# SCH_B_Register_2021-10-06.net
KiCad netlist of a schematic drawn in EasyEDA
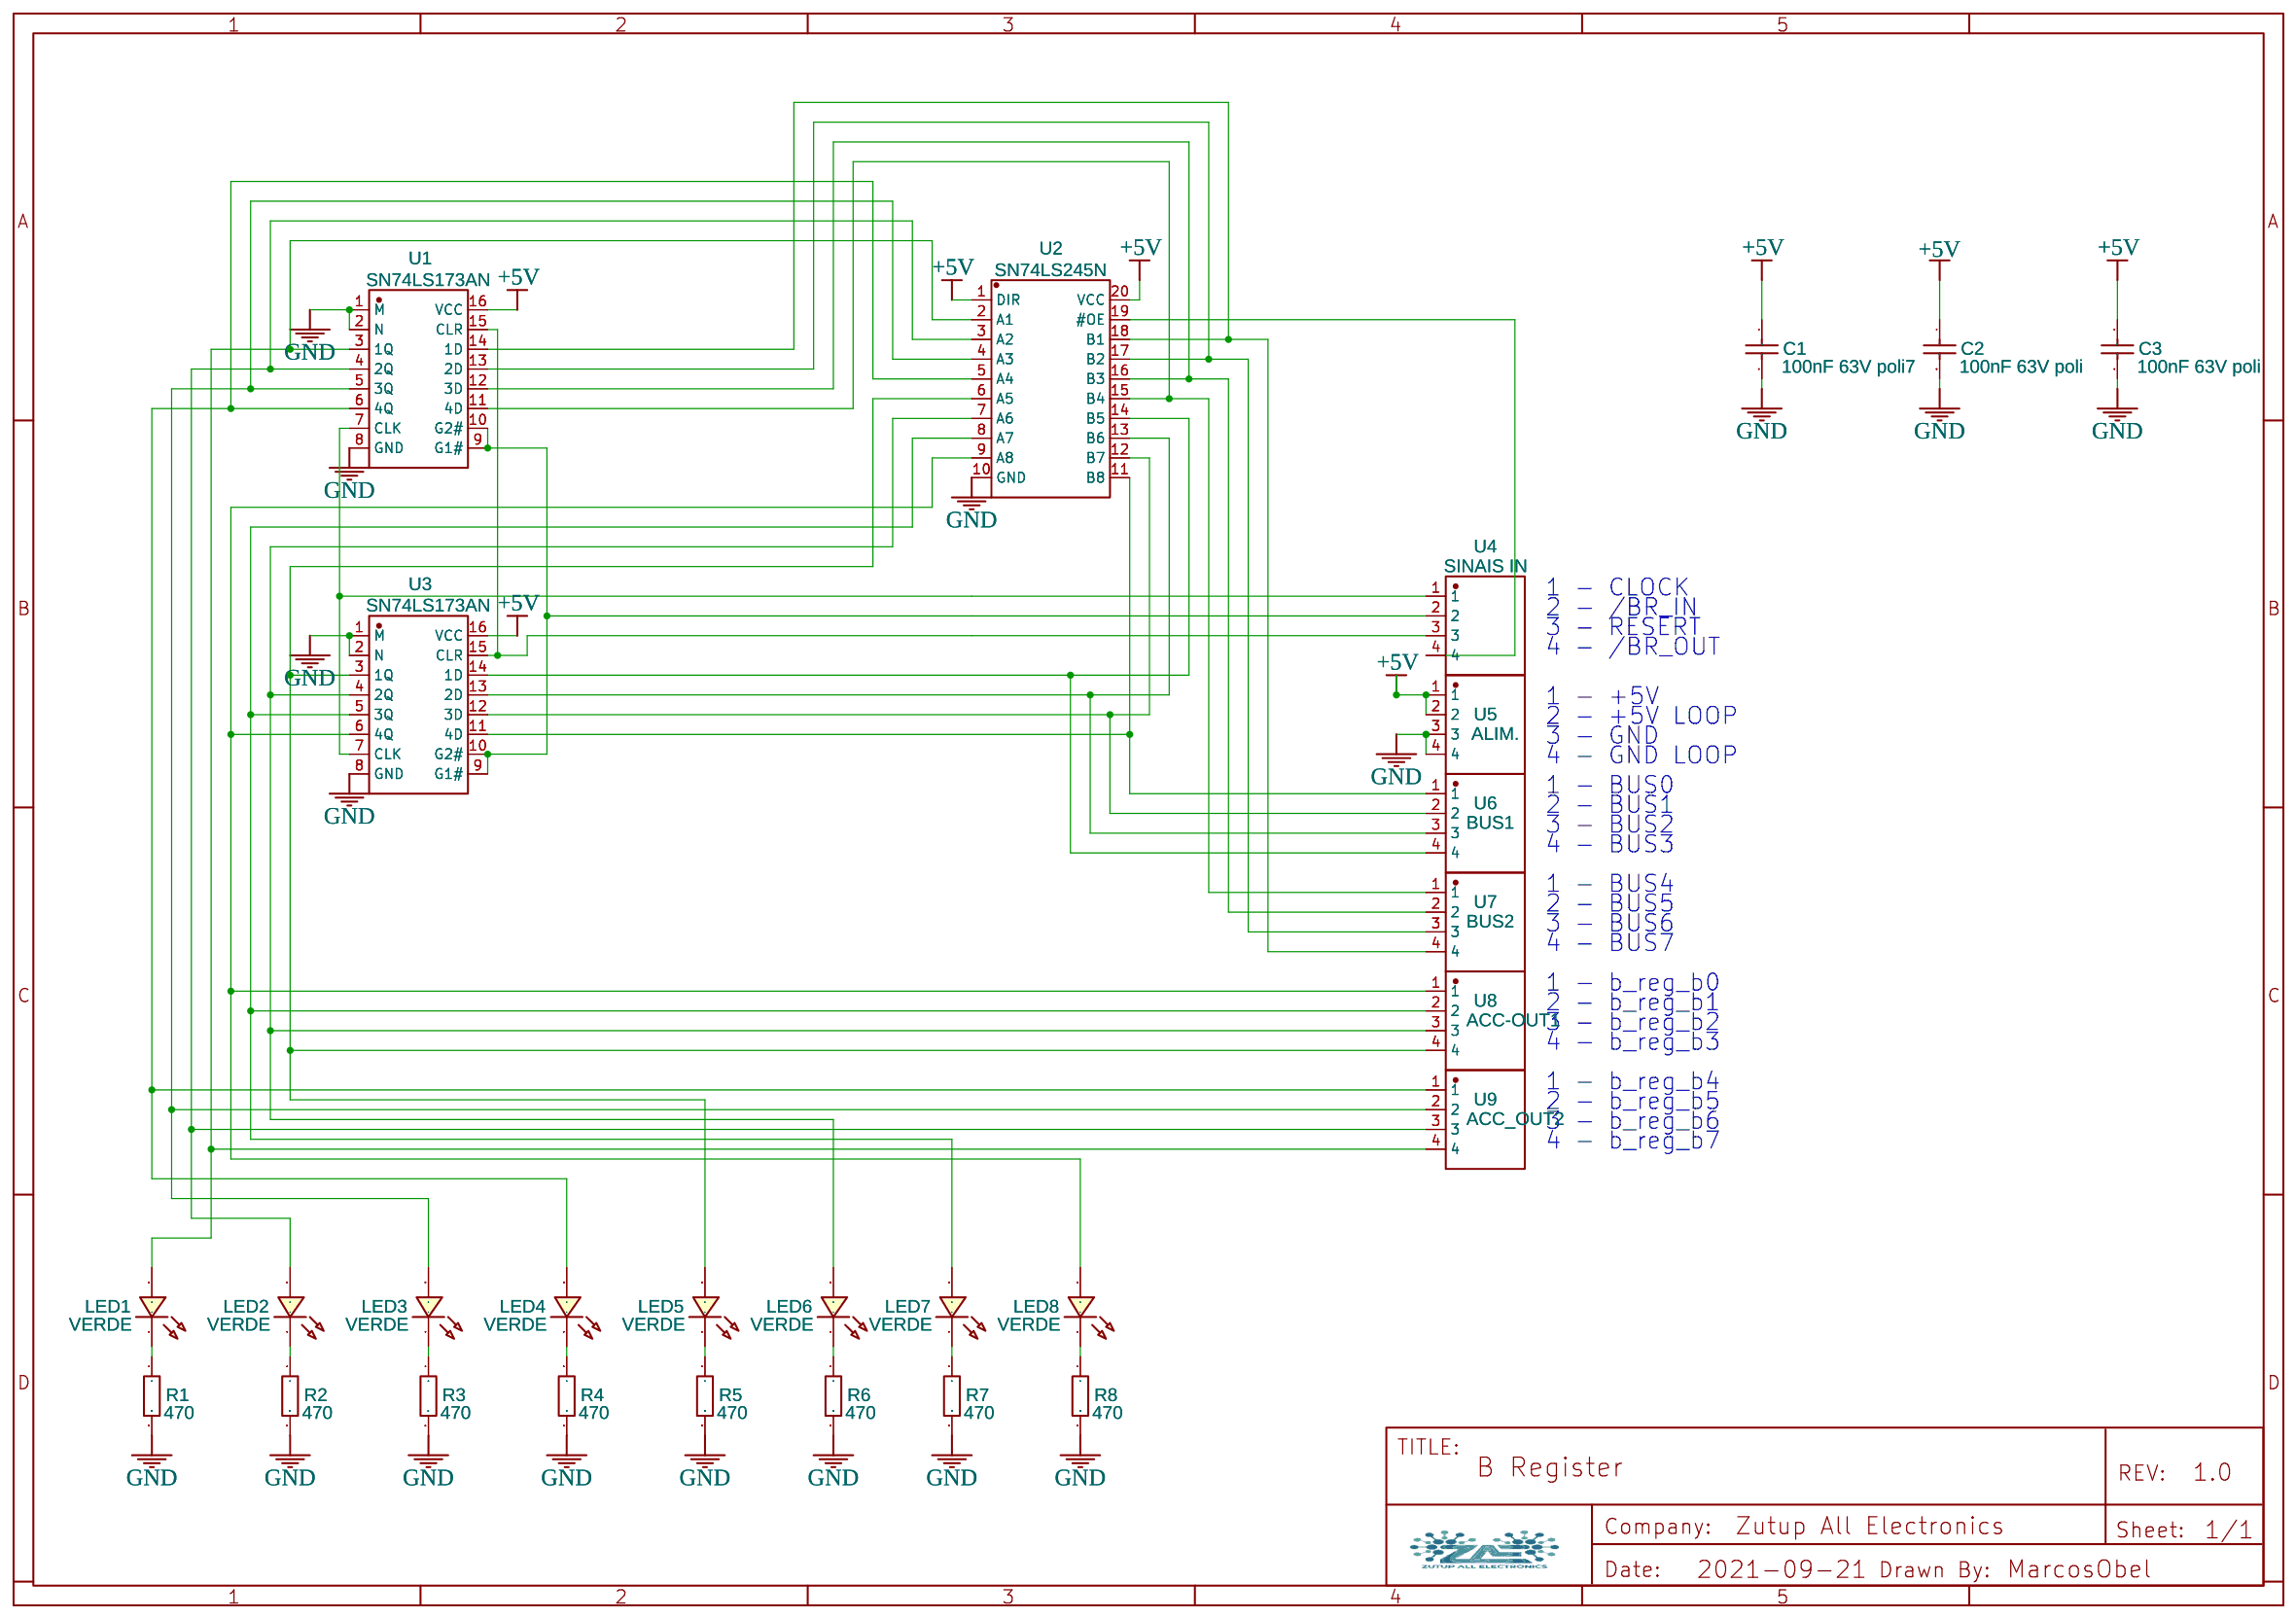
[diagram p0: schematic sheet]

(export (version "E")
  (design (tool "Eeschema 10.0.6"))
  (components
    (comp (ref "C1")
      (value "100nF 63V poli7")
      (fields
        (field (name "BOM_Manufacturer Part") "SR305C105KAR")
        (field (name "BOM_Supplier Part") "C444741")
      )
      (libsource (lib "") (part "SR305C105KAR"))
    )
    (comp (ref "C2")
      (value "100nF 63V poli")
      (fields
        (field (name "BOM_Manufacturer Part") "SR305C105KAR")
        (field (name "BOM_Supplier Part") "C444741")
      )
      (libsource (lib "") (part "SR305C105KAR"))
    )
    (comp (ref "C3")
      (value "100nF 63V poli")
      (fields
        (field (name "BOM_Manufacturer Part") "SR305C105KAR")
        (field (name "BOM_Supplier Part") "C444741")
      )
      (libsource (lib "") (part "SR305C105KAR"))
    )
    (comp (ref "LED1")
      (value "VERDE")
      (fields (field (name "BOM_Manufacturer Part") "264-7GD") (field (name "BOM_Supplier Part") "C605465"))
      (libsource (lib "") (part "264-7GD"))
    )
    (comp (ref "LED2")
      (value "VERDE")
      (fields (field (name "BOM_Manufacturer Part") "264-7GD") (field (name "BOM_Supplier Part") "C605465"))
      (libsource (lib "") (part "264-7GD"))
    )
    (comp (ref "LED3")
      (value "VERDE")
      (fields (field (name "BOM_Manufacturer Part") "264-7GD") (field (name "BOM_Supplier Part") "C605465"))
      (libsource (lib "") (part "264-7GD"))
    )
    (comp (ref "LED4")
      (value "VERDE")
      (fields (field (name "BOM_Manufacturer Part") "264-7GD") (field (name "BOM_Supplier Part") "C605465"))
      (libsource (lib "") (part "264-7GD"))
    )
    (comp (ref "LED5")
      (value "VERDE")
      (fields (field (name "BOM_Manufacturer Part") "264-7GD") (field (name "BOM_Supplier Part") "C605465"))
      (libsource (lib "") (part "264-7GD"))
    )
    (comp (ref "LED6")
      (value "VERDE")
      (fields (field (name "BOM_Manufacturer Part") "264-7GD") (field (name "BOM_Supplier Part") "C605465"))
      (libsource (lib "") (part "264-7GD"))
    )
    (comp (ref "LED7")
      (value "VERDE")
      (fields (field (name "BOM_Manufacturer Part") "264-7GD") (field (name "BOM_Supplier Part") "C605465"))
      (libsource (lib "") (part "264-7GD"))
    )
    (comp (ref "LED8")
      (value "VERDE")
      (fields (field (name "BOM_Manufacturer Part") "264-7GD") (field (name "BOM_Supplier Part") "C605465"))
      (libsource (lib "") (part "264-7GD"))
    )
    (comp (ref "R1")
      (value "470")
      (fields
        (field (name "BOM_Manufacturer Part") "CFR02SJ0823A10")
        (field (name "BOM_Supplier Part") "C69876")
      )
      (libsource (lib "") (part "CFR02SJ0823A10"))
    )
    (comp (ref "R2")
      (value "470")
      (fields
        (field (name "BOM_Manufacturer Part") "CFR02SJ0823A10")
        (field (name "BOM_Supplier Part") "C69876")
      )
      (libsource (lib "") (part "CFR02SJ0823A10"))
    )
    (comp (ref "R3")
      (value "470")
      (fields
        (field (name "BOM_Manufacturer Part") "CFR02SJ0823A10")
        (field (name "BOM_Supplier Part") "C69876")
      )
      (libsource (lib "") (part "CFR02SJ0823A10"))
    )
    (comp (ref "R4")
      (value "470")
      (fields
        (field (name "BOM_Manufacturer Part") "CFR02SJ0823A10")
        (field (name "BOM_Supplier Part") "C69876")
      )
      (libsource (lib "") (part "CFR02SJ0823A10"))
    )
    (comp (ref "R5")
      (value "470")
      (fields
        (field (name "BOM_Manufacturer Part") "CFR02SJ0823A10")
        (field (name "BOM_Supplier Part") "C69876")
      )
      (libsource (lib "") (part "CFR02SJ0823A10"))
    )
    (comp (ref "R6")
      (value "470")
      (fields
        (field (name "BOM_Manufacturer Part") "CFR02SJ0823A10")
        (field (name "BOM_Supplier Part") "C69876")
      )
      (libsource (lib "") (part "CFR02SJ0823A10"))
    )
    (comp (ref "R7")
      (value "470")
      (fields
        (field (name "BOM_Manufacturer Part") "CFR02SJ0823A10")
        (field (name "BOM_Supplier Part") "C69876")
      )
      (libsource (lib "") (part "CFR02SJ0823A10"))
    )
    (comp (ref "R8")
      (value "470")
      (fields
        (field (name "BOM_Manufacturer Part") "CFR02SJ0823A10")
        (field (name "BOM_Supplier Part") "C69876")
      )
      (libsource (lib "") (part "CFR02SJ0823A10"))
    )
    (comp (ref "U1")
      (value "SN74LS173AN")
      (fields (field (name "BOM_Supplier Part") "C1550125"))
      (libsource (lib "") (part "SN74LS173AN"))
    )
    (comp (ref "U2")
      (value "SN74LS245N")
      (fields (field (name "BOM_Supplier Part") "C352966"))
      (libsource (lib "") (part "SN74LS245N"))
    )
    (comp (ref "U3")
      (value "SN74LS173AN")
      (fields (field (name "BOM_Supplier Part") "C1550125"))
      (libsource (lib "") (part "SN74LS173AN"))
    )
    (comp (ref "U4")
      (value "SINAIS IN")
      (fields (field (name "BOM_Manufacturer Part") "171825-4") (field (name "BOM_Supplier Part") "C210162"))
      (libsource (lib "") (part "171825-4"))
    )
    (comp (ref "U5")
      (value "ALIM.")
      (fields (field (name "BOM_Manufacturer Part") "171825-4") (field (name "BOM_Supplier Part") "C210162"))
      (libsource (lib "") (part "171825-4"))
    )
    (comp (ref "U6")
      (value "BUS1")
      (fields (field (name "BOM_Manufacturer Part") "171825-4") (field (name "BOM_Supplier Part") "C210162"))
      (libsource (lib "") (part "171825-4"))
    )
    (comp (ref "U7")
      (value "BUS2")
      (fields (field (name "BOM_Manufacturer Part") "171825-4") (field (name "BOM_Supplier Part") "C210162"))
      (libsource (lib "") (part "171825-4"))
    )
    (comp (ref "U8")
      (value "ACC-OUT1")
      (fields (field (name "BOM_Manufacturer Part") "171825-4") (field (name "BOM_Supplier Part") "C210162"))
      (libsource (lib "") (part "171825-4"))
    )
    (comp (ref "U9")
      (value "ACC_OUT2")
      (fields (field (name "BOM_Manufacturer Part") "171825-4") (field (name "BOM_Supplier Part") "C210162"))
      (libsource (lib "") (part "171825-4"))
    )
  )
  (nets
    (net (code "1") (name "+5V") (class "Default")
      (node (ref "C1") (pin "1") (pinfunction "1_1") (pintype "input"))
      (node (ref "C2") (pin "1") (pinfunction "1_1") (pintype "input"))
      (node (ref "C3") (pin "1") (pinfunction "1_1") (pintype "input"))
      (node (ref "U1") (pin "16") (pinfunction "VCC_16") (pintype "unspecified"))
      (node (ref "U2") (pin "1") (pinfunction "DIR_1") (pintype "unspecified"))
      (node (ref "U2") (pin "20") (pinfunction "VCC_20") (pintype "unspecified"))
      (node (ref "U3") (pin "16") (pinfunction "VCC_16") (pintype "unspecified"))
      (node (ref "U5") (pin "1") (pinfunction "1_1") (pintype "unspecified"))
      (node (ref "U5") (pin "2") (pinfunction "2_2") (pintype "unspecified"))
    )
    (net (code "2") (name "GND") (class "Default")
      (node (ref "C1") (pin "2") (pinfunction "2_2") (pintype "input"))
      (node (ref "C2") (pin "2") (pinfunction "2_2") (pintype "input"))
      (node (ref "C3") (pin "2") (pinfunction "2_2") (pintype "input"))
      (node (ref "R1") (pin "2") (pinfunction "2_2") (pintype "input"))
      (node (ref "R2") (pin "2") (pinfunction "2_2") (pintype "input"))
      (node (ref "R3") (pin "2") (pinfunction "2_2") (pintype "input"))
      (node (ref "R4") (pin "2") (pinfunction "2_2") (pintype "input"))
      (node (ref "R5") (pin "2") (pinfunction "2_2") (pintype "input"))
      (node (ref "R6") (pin "2") (pinfunction "2_2") (pintype "input"))
      (node (ref "R7") (pin "2") (pinfunction "2_2") (pintype "input"))
      (node (ref "R8") (pin "2") (pinfunction "2_2") (pintype "input"))
      (node (ref "U1") (pin "1") (pinfunction "M_1") (pintype "unspecified"))
      (node (ref "U1") (pin "2") (pinfunction "N_2") (pintype "unspecified"))
      (node (ref "U1") (pin "8") (pinfunction "GND_8") (pintype "unspecified"))
      (node (ref "U2") (pin "10") (pinfunction "GND_10") (pintype "unspecified"))
      (node (ref "U3") (pin "1") (pinfunction "M_1") (pintype "unspecified"))
      (node (ref "U3") (pin "2") (pinfunction "N_2") (pintype "unspecified"))
      (node (ref "U3") (pin "8") (pinfunction "GND_8") (pintype "unspecified"))
      (node (ref "U5") (pin "3") (pinfunction "3_3") (pintype "unspecified"))
      (node (ref "U5") (pin "4") (pinfunction "4_4") (pintype "unspecified"))
    )
    (net (code "3") (name "Net-(LED1-+)") (class "Default")
      (node (ref "LED1") (pin "2") (pinfunction "+_2") (pintype "unspecified"))
      (node (ref "U1") (pin "3") (pinfunction "1Q_3") (pintype "unspecified"))
      (node (ref "U2") (pin "2") (pinfunction "A1_2") (pintype "unspecified"))
      (node (ref "U9") (pin "4") (pinfunction "4_4") (pintype "unspecified"))
    )
    (net (code "4") (name "Net-(LED1--)") (class "Default")
      (node (ref "LED1") (pin "1") (pinfunction "-_1") (pintype "unspecified"))
      (node (ref "R1") (pin "1") (pinfunction "1_1") (pintype "input"))
    )
    (net (code "5") (name "Net-(LED2-+)") (class "Default")
      (node (ref "LED2") (pin "2") (pinfunction "+_2") (pintype "unspecified"))
      (node (ref "U1") (pin "4") (pinfunction "2Q_4") (pintype "unspecified"))
      (node (ref "U2") (pin "3") (pinfunction "A2_3") (pintype "unspecified"))
      (node (ref "U9") (pin "3") (pinfunction "3_3") (pintype "unspecified"))
    )
    (net (code "6") (name "Net-(LED2--)") (class "Default")
      (node (ref "LED2") (pin "1") (pinfunction "-_1") (pintype "unspecified"))
      (node (ref "R2") (pin "1") (pinfunction "1_1") (pintype "input"))
    )
    (net (code "7") (name "Net-(LED3-+)") (class "Default")
      (node (ref "LED3") (pin "2") (pinfunction "+_2") (pintype "unspecified"))
      (node (ref "U1") (pin "5") (pinfunction "3Q_5") (pintype "unspecified"))
      (node (ref "U2") (pin "4") (pinfunction "A3_4") (pintype "unspecified"))
      (node (ref "U9") (pin "2") (pinfunction "2_2") (pintype "unspecified"))
    )
    (net (code "8") (name "Net-(LED3--)") (class "Default")
      (node (ref "LED3") (pin "1") (pinfunction "-_1") (pintype "unspecified"))
      (node (ref "R3") (pin "1") (pinfunction "1_1") (pintype "input"))
    )
    (net (code "9") (name "Net-(LED4-+)") (class "Default")
      (node (ref "LED4") (pin "2") (pinfunction "+_2") (pintype "unspecified"))
      (node (ref "U1") (pin "6") (pinfunction "4Q_6") (pintype "unspecified"))
      (node (ref "U2") (pin "5") (pinfunction "A4_5") (pintype "unspecified"))
      (node (ref "U9") (pin "1") (pinfunction "1_1") (pintype "unspecified"))
    )
    (net (code "10") (name "Net-(LED4--)") (class "Default")
      (node (ref "LED4") (pin "1") (pinfunction "-_1") (pintype "unspecified"))
      (node (ref "R4") (pin "1") (pinfunction "1_1") (pintype "input"))
    )
    (net (code "11") (name "Net-(LED5-+)") (class "Default")
      (node (ref "LED5") (pin "2") (pinfunction "+_2") (pintype "unspecified"))
      (node (ref "U2") (pin "6") (pinfunction "A5_6") (pintype "unspecified"))
      (node (ref "U3") (pin "3") (pinfunction "1Q_3") (pintype "unspecified"))
      (node (ref "U8") (pin "4") (pinfunction "4_4") (pintype "unspecified"))
    )
    (net (code "12") (name "Net-(LED5--)") (class "Default")
      (node (ref "LED5") (pin "1") (pinfunction "-_1") (pintype "unspecified"))
      (node (ref "R5") (pin "1") (pinfunction "1_1") (pintype "input"))
    )
    (net (code "13") (name "Net-(LED6-+)") (class "Default")
      (node (ref "LED6") (pin "2") (pinfunction "+_2") (pintype "unspecified"))
      (node (ref "U2") (pin "7") (pinfunction "A6_7") (pintype "unspecified"))
      (node (ref "U3") (pin "4") (pinfunction "2Q_4") (pintype "unspecified"))
      (node (ref "U8") (pin "3") (pinfunction "3_3") (pintype "unspecified"))
    )
    (net (code "14") (name "Net-(LED6--)") (class "Default")
      (node (ref "LED6") (pin "1") (pinfunction "-_1") (pintype "unspecified"))
      (node (ref "R6") (pin "1") (pinfunction "1_1") (pintype "input"))
    )
    (net (code "15") (name "Net-(LED7-+)") (class "Default")
      (node (ref "LED7") (pin "2") (pinfunction "+_2") (pintype "unspecified"))
      (node (ref "U2") (pin "8") (pinfunction "A7_8") (pintype "unspecified"))
      (node (ref "U3") (pin "5") (pinfunction "3Q_5") (pintype "unspecified"))
      (node (ref "U8") (pin "2") (pinfunction "2_2") (pintype "unspecified"))
    )
    (net (code "16") (name "Net-(LED7--)") (class "Default")
      (node (ref "LED7") (pin "1") (pinfunction "-_1") (pintype "unspecified"))
      (node (ref "R7") (pin "1") (pinfunction "1_1") (pintype "input"))
    )
    (net (code "17") (name "Net-(LED8-+)") (class "Default")
      (node (ref "LED8") (pin "2") (pinfunction "+_2") (pintype "unspecified"))
      (node (ref "U2") (pin "9") (pinfunction "A8_9") (pintype "unspecified"))
      (node (ref "U3") (pin "6") (pinfunction "4Q_6") (pintype "unspecified"))
      (node (ref "U8") (pin "1") (pinfunction "1_1") (pintype "unspecified"))
    )
    (net (code "18") (name "Net-(LED8--)") (class "Default")
      (node (ref "LED8") (pin "1") (pinfunction "-_1") (pintype "unspecified"))
      (node (ref "R8") (pin "1") (pinfunction "1_1") (pintype "input"))
    )
    (net (code "19") (name "Net-(U1-1D)") (class "Default")
      (node (ref "U1") (pin "14") (pinfunction "1D_14") (pintype "unspecified"))
      (node (ref "U2") (pin "18") (pinfunction "B1_18") (pintype "unspecified"))
      (node (ref "U7") (pin "4") (pinfunction "4_4") (pintype "unspecified"))
    )
    (net (code "20") (name "Net-(U1-2D)") (class "Default")
      (node (ref "U1") (pin "13") (pinfunction "2D_13") (pintype "unspecified"))
      (node (ref "U2") (pin "17") (pinfunction "B2_17") (pintype "unspecified"))
      (node (ref "U7") (pin "3") (pinfunction "3_3") (pintype "unspecified"))
    )
    (net (code "21") (name "Net-(U1-3D)") (class "Default")
      (node (ref "U1") (pin "12") (pinfunction "3D_12") (pintype "unspecified"))
      (node (ref "U2") (pin "16") (pinfunction "B3_16") (pintype "unspecified"))
      (node (ref "U7") (pin "2") (pinfunction "2_2") (pintype "unspecified"))
    )
    (net (code "22") (name "Net-(U1-4D)") (class "Default")
      (node (ref "U1") (pin "11") (pinfunction "4D_11") (pintype "unspecified"))
      (node (ref "U2") (pin "15") (pinfunction "B4_15") (pintype "unspecified"))
      (node (ref "U7") (pin "1") (pinfunction "1_1") (pintype "unspecified"))
    )
    (net (code "23") (name "Net-(U1-CLK)") (class "Default")
      (node (ref "U1") (pin "7") (pinfunction "CLK_7") (pintype "unspecified"))
      (node (ref "U3") (pin "7") (pinfunction "CLK_7") (pintype "unspecified"))
      (node (ref "U4") (pin "1") (pinfunction "1_1") (pintype "unspecified"))
    )
    (net (code "24") (name "Net-(U1-CLR)") (class "Default")
      (node (ref "U1") (pin "15") (pinfunction "CLR_15") (pintype "unspecified"))
      (node (ref "U3") (pin "15") (pinfunction "CLR_15") (pintype "unspecified"))
      (node (ref "U4") (pin "3") (pinfunction "3_3") (pintype "unspecified"))
    )
    (net (code "25") (name "Net-(U1-G1#)") (class "Default")
      (node (ref "U1") (pin "10") (pinfunction "G2#_10") (pintype "unspecified"))
      (node (ref "U1") (pin "9") (pinfunction "G1#_9") (pintype "unspecified"))
      (node (ref "U3") (pin "10") (pinfunction "G2#_10") (pintype "unspecified"))
      (node (ref "U3") (pin "9") (pinfunction "G1#_9") (pintype "unspecified"))
      (node (ref "U4") (pin "2") (pinfunction "2_2") (pintype "unspecified"))
    )
    (net (code "26") (name "Net-(U2-#OE)") (class "Default")
      (node (ref "U2") (pin "19") (pinfunction "#OE_19") (pintype "unspecified"))
      (node (ref "U4") (pin "4") (pinfunction "4_4") (pintype "unspecified"))
    )
    (net (code "27") (name "Net-(U2-B5)") (class "Default")
      (node (ref "U2") (pin "14") (pinfunction "B5_14") (pintype "unspecified"))
      (node (ref "U3") (pin "14") (pinfunction "1D_14") (pintype "unspecified"))
      (node (ref "U6") (pin "4") (pinfunction "4_4") (pintype "unspecified"))
    )
    (net (code "28") (name "Net-(U2-B6)") (class "Default")
      (node (ref "U2") (pin "13") (pinfunction "B6_13") (pintype "unspecified"))
      (node (ref "U3") (pin "13") (pinfunction "2D_13") (pintype "unspecified"))
      (node (ref "U6") (pin "3") (pinfunction "3_3") (pintype "unspecified"))
    )
    (net (code "29") (name "Net-(U2-B7)") (class "Default")
      (node (ref "U2") (pin "12") (pinfunction "B7_12") (pintype "unspecified"))
      (node (ref "U3") (pin "12") (pinfunction "3D_12") (pintype "unspecified"))
      (node (ref "U6") (pin "2") (pinfunction "2_2") (pintype "unspecified"))
    )
    (net (code "30") (name "Net-(U2-B8)") (class "Default")
      (node (ref "U2") (pin "11") (pinfunction "B8_11") (pintype "unspecified"))
      (node (ref "U3") (pin "11") (pinfunction "4D_11") (pintype "unspecified"))
      (node (ref "U6") (pin "1") (pinfunction "1_1") (pintype "unspecified"))
    )
  )
)
